# JtagToUPDI.net
KiCad netlist of a schematic drawn in Altium Designer
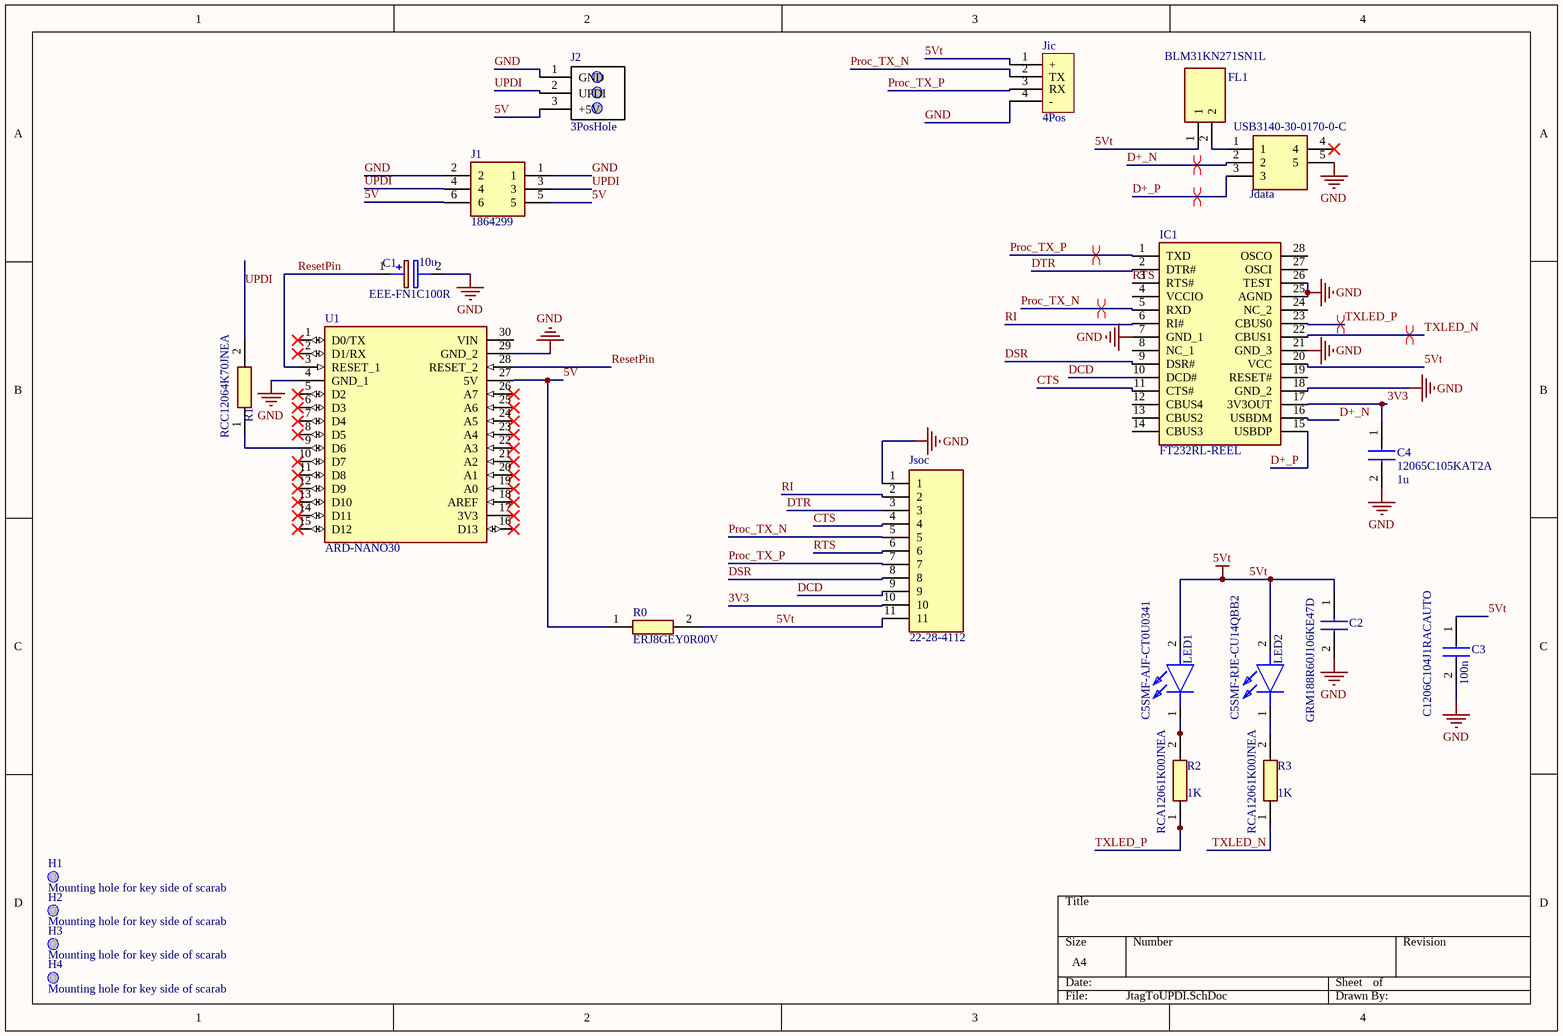
[diagram p0: JtagToUPDI.SchDoc]

(export (version "E")
  (design (tool "Eeschema 10.0.6"))
  (components
    (comp (ref "C1")
      (value "EEE-FN1C100R")
      (footprint "EEE1AA220WR")
      (description "Aluminium Electrolytic Capacitors - SMD 16VDC 10uF 20% 90mA AEC-Q200")
      (fields (field (name "MOUSER PART NUMBER") "667-EEE-FN1C100R") (field (name "ALTIUM_VALUE") "10u"))
      (libsource (lib "Jtag2UPDISchLib") (part "EL-10uF"))
    )
    (comp (ref "C2")
      (value "GRM188R60J106KE47D")
      (footprint "CAPC1608X90N")
      (description "Capacitor")
      (fields (field (name "MOUSER PART NUMBER") "81-GRM188R60J106KE7D"))
      (libsource (lib "Jtag2UPDISchLib") (part "GRM188R60J106KE47D"))
    )
    (comp (ref "C3")
      (value "C1206C104J1RACAUTO")
      (footprint "C1206")
      (description "Multilayer Ceramic Capacitors MLCC - SMD/SMT 100V 0.1uF X7R 1206 5% AEC-Q200")
      (fields (field (name "MOUSER PART NUMBER") "80-C1206C104J1RAUTO") (field (name "ALTIUM_VALUE") "100n"))
      (libsource (lib "Jtag2UPDISchLib") (part "100nF"))
    )
    (comp (ref "C4")
      (value "12065C105KAT2A")
      (footprint "C1206")
      (description "Multilayer Ceramic Capacitors MLCC - SMD/SMT NEW GLOBAL PN KGM31HR71H105KU 50V 1uF X7R 1206 10%")
      (fields
        (field (name "MANUFACTURER_PART_NUMBER") "C1206C104J1RACAUTO")
        (field (name "MOUSER PART NUMBER") "80-C1206C104J1RAUTO")
        (field (name "ALTIUM_VALUE") "1u")
      )
      (libsource (lib "Jtag2UPDISchLib") (part "1uF1206"))
    )
    (comp (ref "FL1")
      (value "BLM31KN271SN1L")
      (footprint "BLM31KN102BH1L")
      (description "Ferrite Beads 270 OHM 4.5A Alternate Sizing Guide Below")
      (fields (field (name "MOUSER PART NUMBER") "81-BLM31KN271SN1L"))
      (libsource (lib "Jtag2UPDISchLib") (part "FB_270OHM_4A5"))
    )
    (comp (ref "H1")
      (value "Mounting hole for key side of scarab")
      (footprint "MTHup")
      (libsource (lib "Jtag2UPDISchLib") (part "MountHole_SCARABup"))
    )
    (comp (ref "H2")
      (value "Mounting hole for key side of scarab")
      (footprint "MTHup")
      (libsource (lib "Jtag2UPDISchLib") (part "MountHole_SCARABup"))
    )
    (comp (ref "H3")
      (value "Mounting hole for key side of scarab")
      (footprint "MTHup")
      (libsource (lib "Jtag2UPDISchLib") (part "MountHole_SCARABup"))
    )
    (comp (ref "H4")
      (value "Mounting hole for key side of scarab")
      (footprint "MTHup")
      (libsource (lib "Jtag2UPDISchLib") (part "MountHole_SCARABup"))
    )
    (comp (ref "IC1")
      (value "FT232RL-REEL")
      (footprint "SOP65P778X200-28N")
      (description "USB Interface IC USB to Serial UART Enhanced IC SSOP-28")
      (fields (field (name "MOUSER PART NUMBER") "895-FT232RL"))
      (libsource (lib "Jtag2UPDISchLib") (part "FT232RL"))
    )
    (comp (ref "J1")
      (value "1864299")
      (footprint "SamacSys:1864299")
      (description "Connector")
      (fields (field (name "MOUSER PART NUMBER") "651-1864299"))
      (libsource (lib "*") (part "1864299"))
    )
    (comp (ref "J2")
      (value "3PosHole")
      (footprint "CON-PRG-3PIN")
      (libsource (lib "Jtag2UPDISchLib") (part "3PosHole"))
    )
    (comp (ref "Jdata")
      (value "USB3140-30-0170-0-C")
      (footprint "USB31403001700C")
      (description "USB Connectors Micro B Skt, Vertical, SMT, 30u\", W/1.7mm stake, no MEF, T&R+cap")
      (fields (field (name "MOUSER PART NUMBER") "640-USB31403001700C"))
      (libsource (lib "Jtag2UPDISchLib") (part "USB_B_Micro"))
    )
    (comp (ref "Jic")
      (value "4Pos")
      (footprint "CON-PRG-4PIN")
      (libsource (lib "Jtag2UPDISchLib") (part "4Pos"))
    )
    (comp (ref "Jsoc")
      (value "22-28-4112")
      (footprint "HDRV11W66P0X254_1X11_2794X249X978P")
      (description "Connector")
      (fields (field (name "MOUSER PART NUMBER") "538-22-28-4112"))
      (libsource (lib "Jtag2UPDISchLib") (part "22-28-4112"))
    )
    (comp (ref "LED1")
      (value "C5SMF-AJF-CT0U0341")
      (footprint "C5SMFRJECU14QBB2")
      (description "Standard LEDs - Through Hole Amber Oval")
      (fields
        (field (name "MANUFACTURER_PART_NUMBER") "C5SMF-RJE-CU14QBB2")
        (field (name "MOUSER PART NUMBER") "941-C5SMFRJECU14QBB2")
      )
      (libsource (lib "Jtag2UPDISchLib") (part "LED_Y"))
    )
    (comp (ref "LED2")
      (value "C5SMF-RJE-CU14QBB2")
      (footprint "C5SMFRJECU14QBB2")
      (description "LED")
      (fields (field (name "MOUSER PART NUMBER") "941-C5SMFRJECU14QBB2"))
      (libsource (lib "Jtag2UPDISchLib") (part "LED_R"))
    )
    (comp (ref "R0")
      (value "ERJ8GEY0R00V")
      (footprint "RESC3116X70N")
      (description "Thick Film Resistors - SMD 1206 Zero ohm Jumper 0.05 AEC-Q200")
      (libsource (lib "Jtag2UPDISchLib") (part "0Ohm1206"))
    )
    (comp (ref "R1")
      (value "RCC12064K70JNEA")
      (footprint "RESC3116X70N")
      (description "Thick Film Resistors - SMD 4.7Kohms 1% 100ppm")
      (fields (field (name "MANUFACTURER_PART_NUMBER") "ERJ8GEY0R00V"))
      (libsource (lib "Jtag2UPDISchLib") (part "R4K7"))
    )
    (comp (ref "R2")
      (value "RCA12061K00JNEA")
      (footprint "RESC3116X65N")
      (description "Thick Film Resistors - SMD RCA1206 1K0 5% 200 ET1 e3")
      (fields (field (name "MANUFACTURER_PART_NUMBER") "ERJ8GEY0R00V") (field (name "ALTIUM_VALUE") "1K"))
      (libsource (lib "Jtag2UPDISchLib") (part "1K"))
    )
    (comp (ref "R3")
      (value "RCA12061K00JNEA")
      (footprint "RESC3116X65N")
      (description "Thick Film Resistors - SMD RCA1206 1K0 5% 200 ET1 e3")
      (fields (field (name "MANUFACTURER_PART_NUMBER") "ERJ8GEY0R00V") (field (name "ALTIUM_VALUE") "1K"))
      (libsource (lib "Jtag2UPDISchLib") (part "1K"))
    )
    (comp (ref "U1")
      (value "ARD-NANO30")
      (footprint "MODULE_A000005")
      (description "Small, complete, and breadboard-friendly board based on the ATmega328 (Arduino Nano 3.x).")
      (fields (field (name "MP") "A000005") (field (name "MF") "Arduino"))
      (libsource (lib "Jtag2UPDISchLib") (part "A000005"))
    )
  )
  (nets
    (net (code "1") (name "/3V3") (class "Default")
      (node (ref "C4") (pin "1") (pinfunction "1_1") (pintype "passive"))
      (node (ref "IC1") (pin "17") (pinfunction "3V3OUT_17") (pintype "passive"))
      (node (ref "Jsoc") (pin "10") (pinfunction "10_10") (pintype "passive"))
    )
    (net (code "2") (name "/5V") (class "Default")
      (node (ref "J1") (pin "5") (pinfunction "5_5") (pintype "passive"))
      (node (ref "J1") (pin "6") (pinfunction "6_6") (pintype "passive"))
      (node (ref "J2") (pin "3") (pinfunction "+5V_3") (pintype "passive"))
      (node (ref "R0") (pin "1") (pinfunction "1_1") (pintype "passive"))
      (node (ref "U1") (pin "27") (pinfunction "5V_27") (pintype "power_in"))
    )
    (net (code "3") (name "/CTS") (class "Default")
      (node (ref "IC1") (pin "11") (pinfunction "CTS#_11") (pintype "passive"))
      (node (ref "Jsoc") (pin "4") (pinfunction "4_4") (pintype "passive"))
    )
    (net (code "4") (name "/D+_N") (class "Default")
      (node (ref "IC1") (pin "16") (pinfunction "USBDM_16") (pintype "passive"))
      (node (ref "Jdata") (pin "2") (pinfunction "2_2") (pintype "passive"))
    )
    (net (code "5") (name "/D+_P") (class "Default")
      (node (ref "IC1") (pin "15") (pinfunction "USBDP_15") (pintype "passive"))
      (node (ref "Jdata") (pin "3") (pinfunction "3_3") (pintype "passive"))
    )
    (net (code "6") (name "/DCD") (class "Default")
      (node (ref "IC1") (pin "10") (pinfunction "DCD#_10") (pintype "passive"))
      (node (ref "Jsoc") (pin "9") (pinfunction "9_9") (pintype "passive"))
    )
    (net (code "7") (name "/DSR") (class "Default")
      (node (ref "IC1") (pin "9") (pinfunction "DSR#_9") (pintype "passive"))
      (node (ref "Jsoc") (pin "8") (pinfunction "8_8") (pintype "passive"))
    )
    (net (code "8") (name "/DTR") (class "Default")
      (node (ref "IC1") (pin "2") (pinfunction "DTR#_2") (pintype "passive"))
      (node (ref "Jsoc") (pin "3") (pinfunction "3_3") (pintype "passive"))
    )
    (net (code "9") (name "/Proc_TX_N") (class "Default")
      (node (ref "IC1") (pin "5") (pinfunction "RXD_5") (pintype "passive"))
      (node (ref "Jic") (pin "2") (pinfunction "TX_2") (pintype "passive"))
      (node (ref "Jsoc") (pin "5") (pinfunction "5_5") (pintype "passive"))
    )
    (net (code "10") (name "/Proc_TX_P") (class "Default")
      (node (ref "IC1") (pin "1") (pinfunction "TXD_1") (pintype "passive"))
      (node (ref "Jic") (pin "3") (pinfunction "RX_3") (pintype "passive"))
      (node (ref "Jsoc") (pin "7") (pinfunction "7_7") (pintype "passive"))
    )
    (net (code "11") (name "/RI") (class "Default")
      (node (ref "IC1") (pin "6") (pinfunction "RI#_6") (pintype "passive"))
      (node (ref "Jsoc") (pin "2") (pinfunction "2_2") (pintype "passive"))
    )
    (net (code "12") (name "/RTS") (class "Default")
      (node (ref "IC1") (pin "3") (pinfunction "RTS#_3") (pintype "passive"))
      (node (ref "Jsoc") (pin "6") (pinfunction "6_6") (pintype "passive"))
    )
    (net (code "13") (name "/ResetPin") (class "Default")
      (node (ref "C1") (pin "1") (pinfunction "+_1") (pintype "passive"))
      (node (ref "U1") (pin "28") (pinfunction "RESET_2_28") (pintype "input"))
      (node (ref "U1") (pin "3") (pinfunction "RESET_1_3") (pintype "input"))
    )
    (net (code "14") (name "/TXLED_N") (class "Default")
      (node (ref "IC1") (pin "22") (pinfunction "CBUS1_22") (pintype "passive"))
      (node (ref "R3") (pin "1") (pinfunction "1_1") (pintype "passive"))
    )
    (net (code "15") (name "/TXLED_P") (class "Default")
      (node (ref "IC1") (pin "23") (pinfunction "CBUS0_23") (pintype "passive"))
      (node (ref "R2") (pin "1") (pinfunction "1_1") (pintype "passive"))
    )
    (net (code "16") (name "/UPDI") (class "Default")
      (node (ref "J1") (pin "3") (pinfunction "3_3") (pintype "passive"))
      (node (ref "J1") (pin "4") (pinfunction "4_4") (pintype "passive"))
      (node (ref "J2") (pin "2") (pinfunction "UPDI_2") (pintype "passive"))
      (node (ref "R1") (pin "2") (pinfunction "2_2") (pintype "passive"))
    )
    (net (code "17") (name "5Vt") (class "Default")
      (node (ref "C2") (pin "1") (pinfunction "1_1") (pintype "passive"))
      (node (ref "C3") (pin "1") (pinfunction "1_1") (pintype "passive"))
      (node (ref "FL1") (pin "1") (pinfunction "1_1") (pintype "passive"))
      (node (ref "IC1") (pin "20") (pinfunction "VCC_20") (pintype "passive"))
      (node (ref "Jic") (pin "1") (pinfunction "+_1") (pintype "passive"))
      (node (ref "Jsoc") (pin "11") (pinfunction "11_11") (pintype "passive"))
      (node (ref "LED1") (pin "2") (pinfunction "A_2") (pintype "passive"))
      (node (ref "LED2") (pin "2") (pinfunction "A_2") (pintype "passive"))
      (node (ref "R0") (pin "2") (pinfunction "2_2") (pintype "passive"))
    )
    (net (code "18") (name "GND") (class "Default")
      (node (ref "C1") (pin "2") (pinfunction "-_2") (pintype "passive"))
      (node (ref "C2") (pin "2") (pinfunction "2_2") (pintype "passive"))
      (node (ref "C3") (pin "2") (pinfunction "2_2") (pintype "passive"))
      (node (ref "C4") (pin "2") (pinfunction "2_2") (pintype "passive"))
      (node (ref "IC1") (pin "18") (pinfunction "GND_2_18") (pintype "passive"))
      (node (ref "IC1") (pin "21") (pinfunction "GND_3_21") (pintype "passive"))
      (node (ref "IC1") (pin "25") (pinfunction "AGND_25") (pintype "passive"))
      (node (ref "IC1") (pin "26") (pinfunction "TEST_26") (pintype "passive"))
      (node (ref "IC1") (pin "7") (pinfunction "GND_1_7") (pintype "passive"))
      (node (ref "J1") (pin "1") (pinfunction "1_1") (pintype "passive"))
      (node (ref "J1") (pin "2") (pinfunction "2_2") (pintype "passive"))
      (node (ref "J2") (pin "1") (pinfunction "GND_1") (pintype "passive"))
      (node (ref "Jdata") (pin "5") (pinfunction "5_5") (pintype "passive"))
      (node (ref "Jic") (pin "4") (pinfunction "-_4") (pintype "passive"))
      (node (ref "Jsoc") (pin "1") (pinfunction "1_1") (pintype "passive"))
      (node (ref "U1") (pin "29") (pinfunction "GND_2_29") (pintype "power_in"))
      (node (ref "U1") (pin "4") (pinfunction "GND_1_4") (pintype "power_in"))
    )
    (net (code "19") (name "Net-(FL1-Pad2)") (class "Default")
      (node (ref "FL1") (pin "2") (pinfunction "2_2") (pintype "passive"))
      (node (ref "Jdata") (pin "1") (pinfunction "1_1") (pintype "passive"))
    )
    (net (code "20") (name "Net-(LED1-K)") (class "Default")
      (node (ref "LED1") (pin "1") (pinfunction "K_1") (pintype "passive"))
      (node (ref "R2") (pin "2") (pinfunction "2_2") (pintype "passive"))
    )
    (net (code "21") (name "Net-(LED2-K)") (class "Default")
      (node (ref "LED2") (pin "1") (pinfunction "K_1") (pintype "passive"))
      (node (ref "R3") (pin "2") (pinfunction "2_2") (pintype "passive"))
    )
    (net (code "22") (name "Net-(U1-D6)") (class "Default")
      (node (ref "R1") (pin "1") (pinfunction "1_1") (pintype "passive"))
      (node (ref "U1") (pin "9") (pinfunction "D6_9") (pintype "bidirectional"))
    )
    (net (code "23") (name "unconnected-(IC1-CBUS2-Pad13)") (class "Default")
      (node (ref "IC1") (pin "13") (pinfunction "CBUS2_13") (pintype "passive"))
    )
    (net (code "24") (name "unconnected-(IC1-CBUS3-Pad14)") (class "Default")
      (node (ref "IC1") (pin "14") (pinfunction "CBUS3_14") (pintype "passive"))
    )
    (net (code "25") (name "unconnected-(IC1-CBUS4-Pad12)") (class "Default")
      (node (ref "IC1") (pin "12") (pinfunction "CBUS4_12") (pintype "passive"))
    )
    (net (code "26") (name "unconnected-(IC1-NC_1-Pad8)") (class "Default")
      (node (ref "IC1") (pin "8") (pinfunction "NC_1_8") (pintype "passive"))
    )
    (net (code "27") (name "unconnected-(IC1-NC_2-Pad24)") (class "Default")
      (node (ref "IC1") (pin "24") (pinfunction "NC_2_24") (pintype "passive"))
    )
    (net (code "28") (name "unconnected-(IC1-OSCI-Pad27)") (class "Default")
      (node (ref "IC1") (pin "27") (pinfunction "OSCI_27") (pintype "passive"))
    )
    (net (code "29") (name "unconnected-(IC1-OSCO-Pad28)") (class "Default")
      (node (ref "IC1") (pin "28") (pinfunction "OSCO_28") (pintype "passive"))
    )
    (net (code "30") (name "unconnected-(IC1-RESET#-Pad19)") (class "Default")
      (node (ref "IC1") (pin "19") (pinfunction "RESET#_19") (pintype "passive"))
    )
    (net (code "31") (name "unconnected-(IC1-VCCIO-Pad4)") (class "Default")
      (node (ref "IC1") (pin "4") (pinfunction "VCCIO_4") (pintype "passive"))
    )
    (net (code "32") (name "unconnected-(Jdata-Pad4)") (class "Default")
      (node (ref "Jdata") (pin "4") (pinfunction "4_4") (pintype "passive+no_connect"))
    )
    (net (code "33") (name "unconnected-(U1-3V3-Pad17)") (class "Default")
      (node (ref "U1") (pin "17") (pinfunction "3V3_17") (pintype "power_in+no_connect"))
    )
    (net (code "34") (name "unconnected-(U1-A0-Pad19)") (class "Default")
      (node (ref "U1") (pin "19") (pinfunction "A0_19") (pintype "input+no_connect"))
    )
    (net (code "35") (name "unconnected-(U1-A1-Pad20)") (class "Default")
      (node (ref "U1") (pin "20") (pinfunction "A1_20") (pintype "input+no_connect"))
    )
    (net (code "36") (name "unconnected-(U1-A2-Pad21)") (class "Default")
      (node (ref "U1") (pin "21") (pinfunction "A2_21") (pintype "input+no_connect"))
    )
    (net (code "37") (name "unconnected-(U1-A3-Pad22)") (class "Default")
      (node (ref "U1") (pin "22") (pinfunction "A3_22") (pintype "input+no_connect"))
    )
    (net (code "38") (name "unconnected-(U1-A4-Pad23)") (class "Default")
      (node (ref "U1") (pin "23") (pinfunction "A4_23") (pintype "input+no_connect"))
    )
    (net (code "39") (name "unconnected-(U1-A5-Pad24)") (class "Default")
      (node (ref "U1") (pin "24") (pinfunction "A5_24") (pintype "input+no_connect"))
    )
    (net (code "40") (name "unconnected-(U1-A6-Pad25)") (class "Default")
      (node (ref "U1") (pin "25") (pinfunction "A6_25") (pintype "input+no_connect"))
    )
    (net (code "41") (name "unconnected-(U1-A7-Pad26)") (class "Default")
      (node (ref "U1") (pin "26") (pinfunction "A7_26") (pintype "input+no_connect"))
    )
    (net (code "42") (name "unconnected-(U1-AREF-Pad18)") (class "Default")
      (node (ref "U1") (pin "18") (pinfunction "AREF_18") (pintype "input+no_connect"))
    )
    (net (code "43") (name "unconnected-(U1-D0{slash}TX-Pad1)") (class "Default")
      (node (ref "U1") (pin "1") (pinfunction "D0/TX_1") (pintype "bidirectional+no_connect"))
    )
    (net (code "44") (name "unconnected-(U1-D1{slash}RX-Pad2)") (class "Default")
      (node (ref "U1") (pin "2") (pinfunction "D1/RX_2") (pintype "bidirectional+no_connect"))
    )
    (net (code "45") (name "unconnected-(U1-D2-Pad5)") (class "Default")
      (node (ref "U1") (pin "5") (pinfunction "D2_5") (pintype "bidirectional+no_connect"))
    )
    (net (code "46") (name "unconnected-(U1-D3-Pad6)") (class "Default")
      (node (ref "U1") (pin "6") (pinfunction "D3_6") (pintype "bidirectional+no_connect"))
    )
    (net (code "47") (name "unconnected-(U1-D4-Pad7)") (class "Default")
      (node (ref "U1") (pin "7") (pinfunction "D4_7") (pintype "bidirectional+no_connect"))
    )
    (net (code "48") (name "unconnected-(U1-D5-Pad8)") (class "Default")
      (node (ref "U1") (pin "8") (pinfunction "D5_8") (pintype "bidirectional+no_connect"))
    )
    (net (code "49") (name "unconnected-(U1-D7-Pad10)") (class "Default")
      (node (ref "U1") (pin "10") (pinfunction "D7_10") (pintype "bidirectional+no_connect"))
    )
    (net (code "50") (name "unconnected-(U1-D8-Pad11)") (class "Default")
      (node (ref "U1") (pin "11") (pinfunction "D8_11") (pintype "bidirectional+no_connect"))
    )
    (net (code "51") (name "unconnected-(U1-D9-Pad12)") (class "Default")
      (node (ref "U1") (pin "12") (pinfunction "D9_12") (pintype "bidirectional+no_connect"))
    )
    (net (code "52") (name "unconnected-(U1-D10-Pad13)") (class "Default")
      (node (ref "U1") (pin "13") (pinfunction "D10_13") (pintype "bidirectional+no_connect"))
    )
    (net (code "53") (name "unconnected-(U1-D11-Pad14)") (class "Default")
      (node (ref "U1") (pin "14") (pinfunction "D11_14") (pintype "bidirectional+no_connect"))
    )
    (net (code "54") (name "unconnected-(U1-D12-Pad15)") (class "Default")
      (node (ref "U1") (pin "15") (pinfunction "D12_15") (pintype "bidirectional+no_connect"))
    )
    (net (code "55") (name "unconnected-(U1-D13-Pad16)") (class "Default")
      (node (ref "U1") (pin "16") (pinfunction "D13_16") (pintype "bidirectional+no_connect"))
    )
    (net (code "56") (name "unconnected-(U1-VIN-Pad30)") (class "Default")
      (node (ref "U1") (pin "30") (pinfunction "VIN_30") (pintype "power_in"))
    )
  )
)
